# Battery_Power.net
KiCad netlist of a schematic drawn in Altium Designer
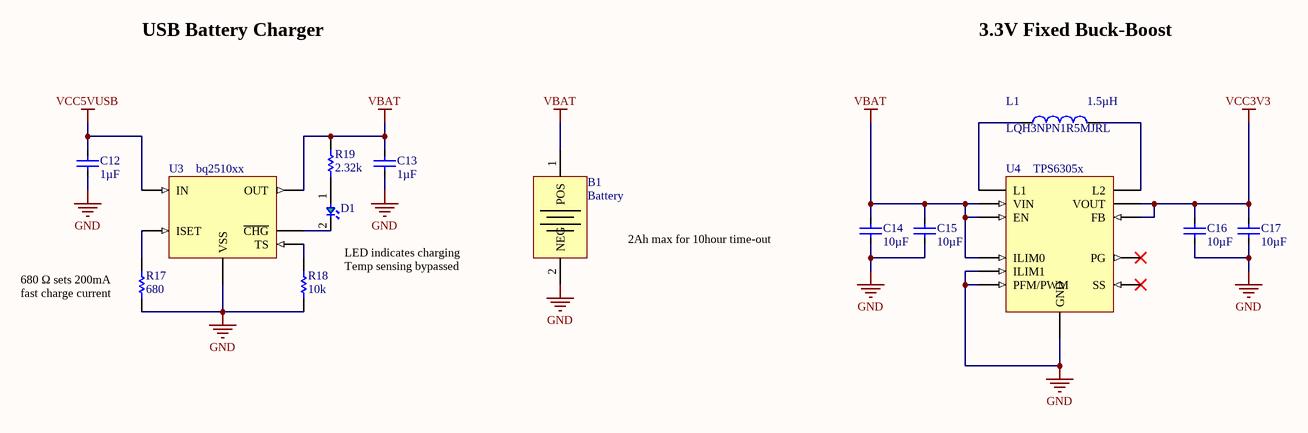
[diagram p0: Battery_Power.SchDoc]

(export (version "E")
  (design (tool "Eeschema 10.0.6"))
  (components
    (comp (ref "B1")
      (value "Battery")
      (footprint "S2B-PH-SM4")
      (description "CONN HEADER PH SIDE 2POS 2MM SMD")
      (fields
        (field (name "MANUFACTURER") "JST Sales America Inc.")
        (field (name "MANUFACTURER PART NUMBER") "S2B-PH-SM4-TB(LF)(SN)")
      )
      (libsource (lib "mechanart_oshw") (part "Battery"))
    )
    (comp (ref "C12")
      (value "1µF")
      (footprint "CAPC1005X50L25N")
      (description "CAP CER 1UF 6.3V X7R 0402")
      (fields
        (field (name "MANUFACTURER") "Murata Electronics North America")
        (field (name "MANUFACTURER PART NUMBER") "GRM155R70J105KA12D")
      )
      (libsource (lib "mechanart_oshw") (part "CapSMT"))
    )
    (comp (ref "C13")
      (value "1µF")
      (footprint "CAPC1005X50L25N")
      (description "CAP CER 1UF 6.3V X7R 0402")
      (fields
        (field (name "MANUFACTURER") "Murata Electronics North America")
        (field (name "MANUFACTURER PART NUMBER") "GRM155R70J105KA12D")
      )
      (libsource (lib "mechanart_oshw") (part "CapSMT"))
    )
    (comp (ref "C14")
      (value "10µF")
      (footprint "CAPC1220X95L30L")
      (description "CAP CER 10UF 6.3V X6S 0508")
      (fields
        (field (name "MANUFACTURER") "Taiyo Yuden")
        (field (name "MANUFACTURER PART NUMBER") "JWK212C6106MD-T")
      )
      (libsource (lib "mechanart_oshw") (part "CapSMT"))
    )
    (comp (ref "C15")
      (value "10µF")
      (footprint "CAPC1220X95L30L")
      (description "CAP CER 10UF 6.3V X6S 0508")
      (fields
        (field (name "MANUFACTURER") "Taiyo Yuden")
        (field (name "MANUFACTURER PART NUMBER") "JWK212C6106MD-T")
      )
      (libsource (lib "mechanart_oshw") (part "CapSMT"))
    )
    (comp (ref "C16")
      (value "10µF")
      (footprint "CAPC1220X95L30L")
      (description "CAP CER 10UF 6.3V X6S 0508")
      (fields
        (field (name "MANUFACTURER") "Taiyo Yuden")
        (field (name "MANUFACTURER PART NUMBER") "JWK212C6106MD-T")
      )
      (libsource (lib "mechanart_oshw") (part "CapSMT"))
    )
    (comp (ref "C17")
      (value "10µF")
      (footprint "CAPC1220X95L30L")
      (description "CAP CER 10UF 6.3V X6S 0508")
      (fields
        (field (name "MANUFACTURER") "Taiyo Yuden")
        (field (name "MANUFACTURER PART NUMBER") "JWK212C6106MD-T")
      )
      (libsource (lib "mechanart_oshw") (part "CapSMT"))
    )
    (comp (ref "D1")
      (value "Green LED")
      (footprint "SML-P11Mxxx")
      (description "LED GREEN CLEAR 0402 SMD")
      (fields
        (field (name "MANUFACTURER") "Rohm Semiconductor")
        (field (name "MANUFACTURER PART NUMBER") "SML-P11MTT86")
      )
      (libsource (lib "mechanart_oshw") (part "LED-GRN"))
    )
    (comp (ref "L1")
      (value "1.5µH")
      (footprint "INDC3030X30L90L")
      (description "FIXED IND 1.5UH 1.1A 49 MOHM SMD")
      (fields
        (field (name "MANUFACTURER") "Murata Electronics North America")
        (field (name "MANUFACTURER PART NUMBER") "LQH3NPN1R5MJRL")
        (field (name "TOLERANCE") "±20%")
      )
      (libsource (lib "mechanart_oshw") (part "Inductor"))
    )
    (comp (ref "R17")
      (value "680")
      (footprint "RESC1005X40L25N")
      (description "RES SMD 680 OHM 1% 1/10W 0402")
      (fields
        (field (name "MANUFACTURER") "Panasonic Electronic Components")
        (field (name "MANUFACTURER PART NUMBER") "ERJ-2RKF6800X")
      )
      (libsource (lib "mechanart_oshw") (part "ResSMT"))
    )
    (comp (ref "R18")
      (value "10k")
      (footprint "RESC1005X40L25N")
      (description "RES SMD 10K OHM 5% 1/16W 0402")
      (fields
        (field (name "MANUFACTURER") "Vishay Dale")
        (field (name "MANUFACTURER PART NUMBER") "CRCW040210K0JNED")
      )
      (libsource (lib "mechanart_oshw") (part "ResSMT"))
    )
    (comp (ref "R19")
      (value "2.32k")
      (footprint "RESC1005X40L25N")
      (description "RES SMD 2.32K OHM 1% 1/10W 0402")
      (fields
        (field (name "MANUFACTURER") "Panasonic Electronic Components")
        (field (name "MANUFACTURER PART NUMBER") "ERJ-2RKF2321X")
      )
      (libsource (lib "mechanart_oshw") (part "ResSMT"))
    )
    (comp (ref "U3")
      (value "bq2510xx")
      (footprint "BGA6C40P3X2_157X88X50B23L")
      (description "IC LI-ION CHARGE MGMT 6DSBGA")
      (fields
        (field (name "MANUFACTURER") "Texas Instruments")
        (field (name "MANUFACTURER PART NUMBER") "BQ25101YFPR")
      )
      (libsource (lib "mechanart_oshw") (part "bq2510xx"))
    )
    (comp (ref "U4")
      (value "TPS6305x")
      (footprint "BGA12C40P4X3_168X128X62B25L")
      (description "IC REG BCK BST 3.3V 0.5A 12DSBGA")
      (fields
        (field (name "MANUFACTURER") "Texas Instruments")
        (field (name "MANUFACTURER PART NUMBER") "TPS63051YFFR")
      )
      (libsource (lib "mechanart_oshw") (part "TPS6305x"))
    )
  )
  (nets
    (net (code "1") (name "GND") (class "Default")
      (node (ref "B1") (pin "2") (pinfunction "NEG_2") (pintype "passive"))
      (node (ref "C12") (pin "2") (pinfunction "2_2") (pintype "passive"))
      (node (ref "C13") (pin "2") (pinfunction "2_2") (pintype "passive"))
      (node (ref "C14") (pin "2") (pinfunction "2_2") (pintype "passive"))
      (node (ref "C15") (pin "2") (pinfunction "2_2") (pintype "passive"))
      (node (ref "C16") (pin "2") (pinfunction "2_2") (pintype "passive"))
      (node (ref "C17") (pin "2") (pinfunction "2_2") (pintype "passive"))
      (node (ref "R17") (pin "1") (pinfunction "1_1") (pintype "passive"))
      (node (ref "R18") (pin "1") (pinfunction "1_1") (pintype "passive"))
      (node (ref "U3") (pin "C2") (pinfunction "VSS_C2") (pintype "power_in"))
      (node (ref "U4") (pin "B1") (pinfunction "GND_B1") (pintype "power_in"))
      (node (ref "U4") (pin "B3") (pinfunction "ILIM1_B3") (pintype "input"))
      (node (ref "U4") (pin "C2") (pinfunction "PFM/PWM_C2") (pintype "input"))
    )
    (net (code "2") (name "Net-(D1-A)") (class "Default")
      (node (ref "D1") (pin "1") (pinfunction "A_1") (pintype "passive"))
      (node (ref "R19") (pin "1") (pinfunction "1_1") (pintype "passive"))
    )
    (net (code "3") (name "Net-(D1-C)") (class "Default")
      (node (ref "D1") (pin "2") (pinfunction "C_2") (pintype "passive"))
      (node (ref "U3") (pin "C1") (pinfunction "~{CHG}_C1") (pintype "open_collector"))
    )
    (net (code "4") (name "Net-(U3-ISET)") (class "Default")
      (node (ref "R17") (pin "2") (pinfunction "2_2") (pintype "passive"))
      (node (ref "U3") (pin "B2") (pinfunction "ISET_B2") (pintype "input"))
    )
    (net (code "5") (name "Net-(U3-TS)") (class "Default")
      (node (ref "R18") (pin "2") (pinfunction "2_2") (pintype "passive"))
      (node (ref "U3") (pin "B1") (pinfunction "TS_B1") (pintype "input"))
    )
    (net (code "6") (name "Net-(U4-L1)") (class "Default")
      (node (ref "L1") (pin "1") (pinfunction "1_1") (pintype "passive"))
      (node (ref "U4") (pin "A1") (pinfunction "L1_A1") (pintype "passive"))
    )
    (net (code "7") (name "Net-(U4-L2)") (class "Default")
      (node (ref "L1") (pin "2") (pinfunction "2_2") (pintype "passive"))
      (node (ref "U4") (pin "C1") (pinfunction "L2_C1") (pintype "passive"))
    )
    (net (code "8") (name "VBAT") (class "Default")
      (node (ref "B1") (pin "1") (pinfunction "POS_1") (pintype "passive"))
      (node (ref "C13") (pin "1") (pinfunction "1_1") (pintype "passive"))
      (node (ref "C14") (pin "1") (pinfunction "1_1") (pintype "passive"))
      (node (ref "C15") (pin "1") (pinfunction "1_1") (pintype "passive"))
      (node (ref "R19") (pin "2") (pinfunction "2_2") (pintype "passive"))
      (node (ref "U3") (pin "A1") (pinfunction "OUT_A1") (pintype "output"))
      (node (ref "U4") (pin "A2") (pinfunction "VIN_A2") (pintype "input"))
      (node (ref "U4") (pin "A3") (pinfunction "EN_A3") (pintype "input"))
      (node (ref "U4") (pin "B2") (pinfunction "ILIM0_B2") (pintype "input"))
    )
    (net (code "9") (name "VCC3V3") (class "Default")
      (node (ref "C16") (pin "1") (pinfunction "1_1") (pintype "passive"))
      (node (ref "C17") (pin "1") (pinfunction "1_1") (pintype "passive"))
      (node (ref "U4") (pin "D1") (pinfunction "VOUT_D1") (pintype "power_in"))
      (node (ref "U4") (pin "D2") (pinfunction "FB_D2") (pintype "input"))
    )
    (net (code "10") (name "VCC5VUSB") (class "Default")
      (node (ref "C12") (pin "1") (pinfunction "1_1") (pintype "passive"))
      (node (ref "U3") (pin "A2") (pinfunction "IN_A2") (pintype "input"))
    )
    (net (code "11") (name "unconnected-(U4-PG-PadC3)") (class "Default")
      (node (ref "U4") (pin "C3") (pinfunction "PG_C3") (pintype "output+no_connect"))
    )
    (net (code "12") (name "unconnected-(U4-SS-PadD3)") (class "Default")
      (node (ref "U4") (pin "D3") (pinfunction "SS_D3") (pintype "input+no_connect"))
    )
  )
)
